# transducer_breakout.net
KiCad netlist of a schematic drawn in EAGLE
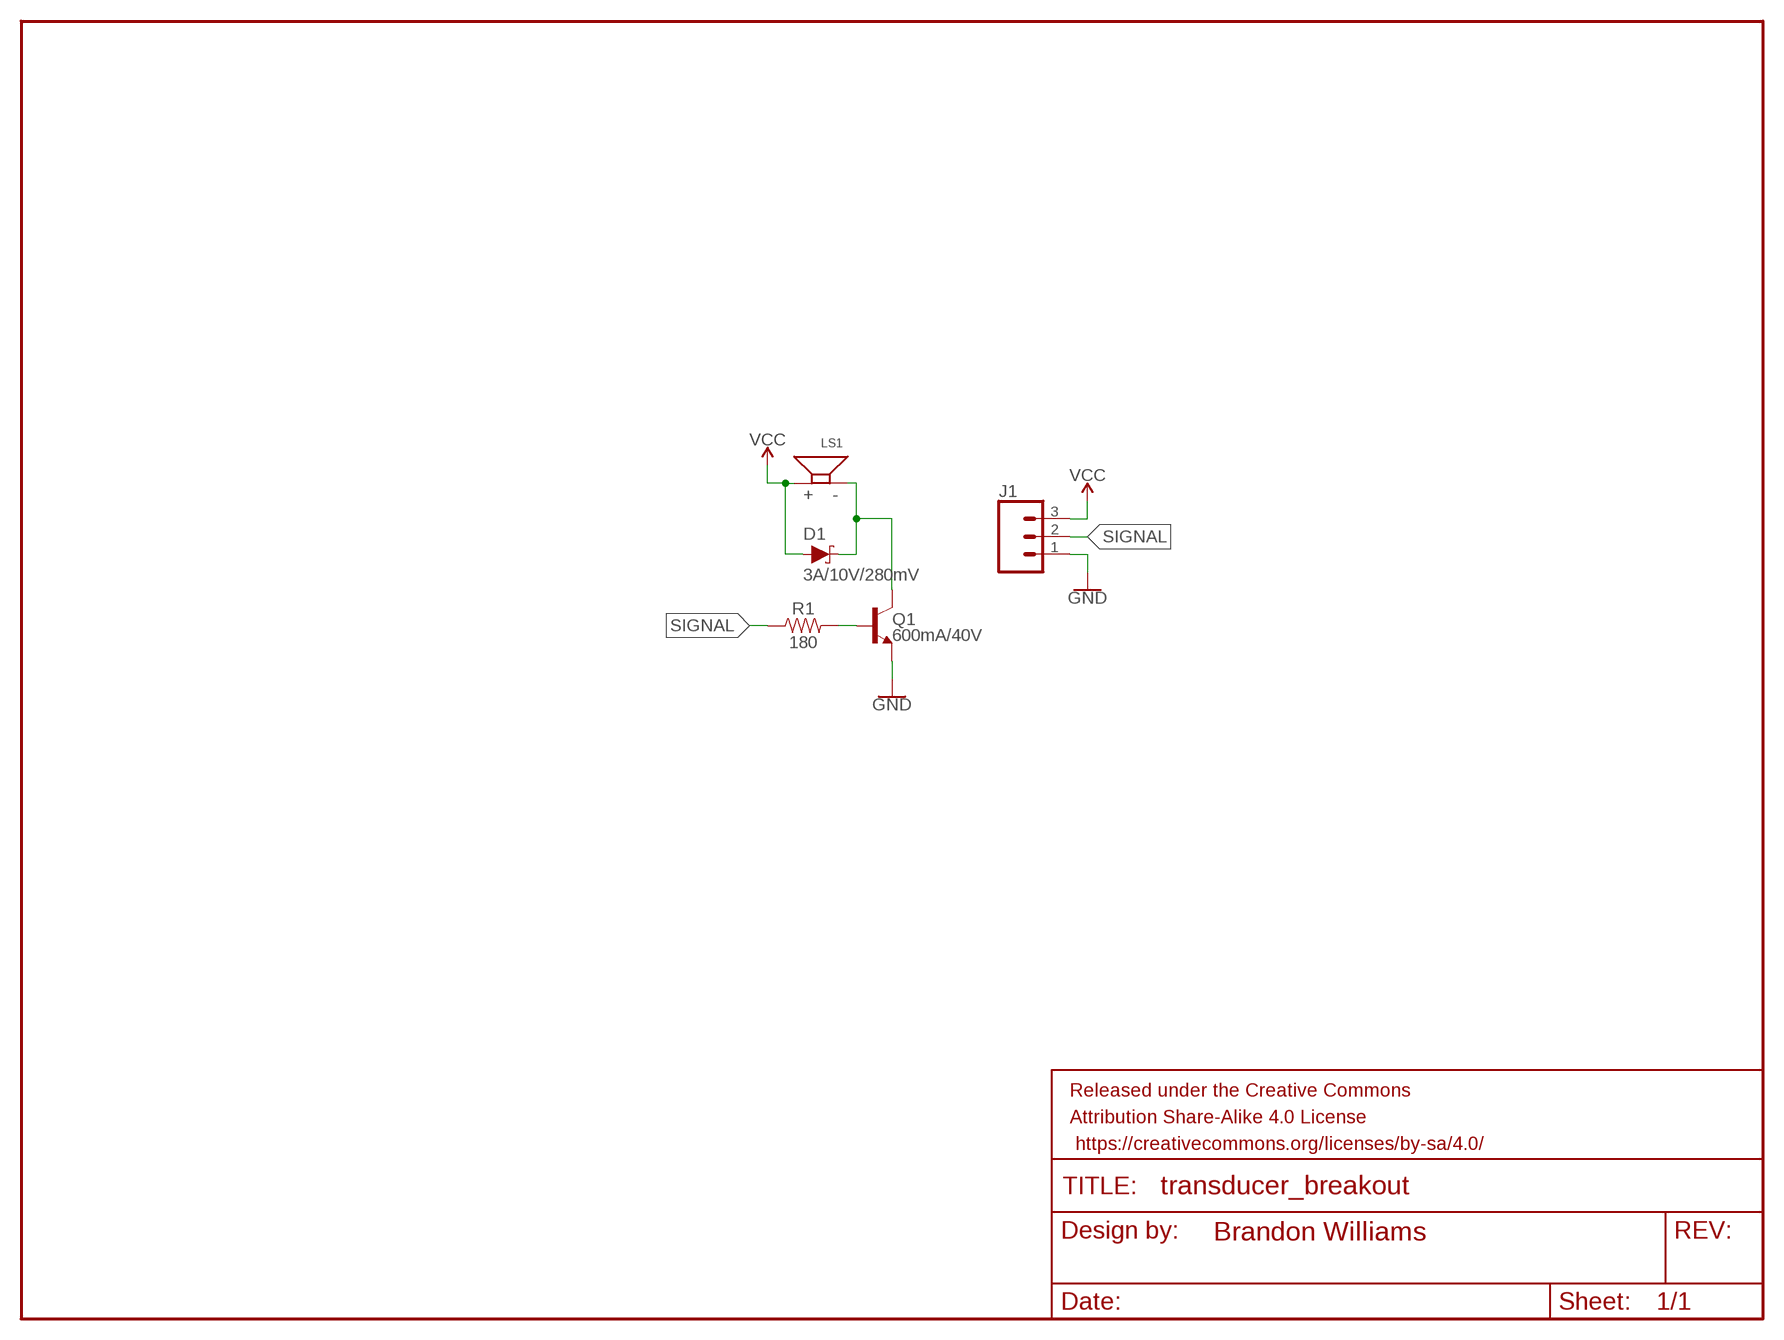
[diagram p0: schematic, sheet 1]

(export (version "E")
  (design (tool "Eeschema 10.0.6"))
  (components
    (comp (ref "D1")
      (value "3A/10V/280mV")
      (footprint "eagle-import:SOD-323")
      (libsource (lib "eagle-import") (part "DIODE-SCHOTTKY-BAT60A"))
    )
    (comp (ref "FRAME1")
      (value "FRAME-LETTERNO_PACKAGE")
      (footprint "eagle-import:DUMMY")
      (fields (field (name "DESIGNER") "Brandon Williams") (field (name "DESIGNER_1") "Brandon Williams"))
      (libsource (lib "eagle-import") (part "FRAME-LETTERNO_PACKAGE"))
    )
    (comp (ref "J1")
      (value "455-1750-1-ND")
      (footprint "eagle-import:1X03")
      (libsource (lib "eagle-import") (part "CONN_03"))
    )
    (comp (ref "LS1")
      (value "TRANSDUCERSMT-0340-T-R")
      (footprint "eagle-import:SMT-0340-T-R")
      (libsource (lib "eagle-import") (part "TRANSDUCERSMT-0340-T-R"))
    )
    (comp (ref "Q1")
      (value "600mA/40V")
      (footprint "eagle-import:SOT23-3")
      (libsource (lib "eagle-import") (part "TRANS_NPN-MMBT2222AL"))
    )
    (comp (ref "R1")
      (value "180")
      (footprint "eagle-import:0603")
      (libsource (lib "eagle-import") (part "180OHM-0603-1/10W-1%"))
    )
  )
  (nets
    (net (code "1") (name "GND") (class "Default")
      (node (ref "J1") (pin "1") (pinfunction "1_1") (pintype "passive"))
      (node (ref "Q1") (pin "2") (pinfunction "E_2") (pintype "passive"))
    )
    (net (code "2") (name "Net-(LS1--)") (class "Default")
      (node (ref "D1") (pin "C") (pinfunction "C_C") (pintype "passive"))
      (node (ref "LS1") (pin "P$1") (pinfunction "-_P$1") (pintype "power_in"))
      (node (ref "Q1") (pin "3") (pinfunction "C_3") (pintype "passive"))
    )
    (net (code "3") (name "Net-(Q1-B)") (class "Default")
      (node (ref "Q1") (pin "1") (pinfunction "B_1") (pintype "passive"))
      (node (ref "R1") (pin "2") (pinfunction "2_2") (pintype "passive"))
    )
    (net (code "4") (name "SIGNAL") (class "Default")
      (node (ref "J1") (pin "2") (pinfunction "2_2") (pintype "passive"))
      (node (ref "R1") (pin "1") (pinfunction "1_1") (pintype "passive"))
    )
    (net (code "5") (name "VCC") (class "Default")
      (node (ref "D1") (pin "A") (pinfunction "A_A") (pintype "passive"))
      (node (ref "J1") (pin "3") (pinfunction "3_3") (pintype "passive"))
      (node (ref "LS1") (pin "P$2") (pinfunction "+_P$2") (pintype "power_in"))
    )
  )
)
